# rtc.net
KiCad netlist of a schematic drawn in Altium Designer
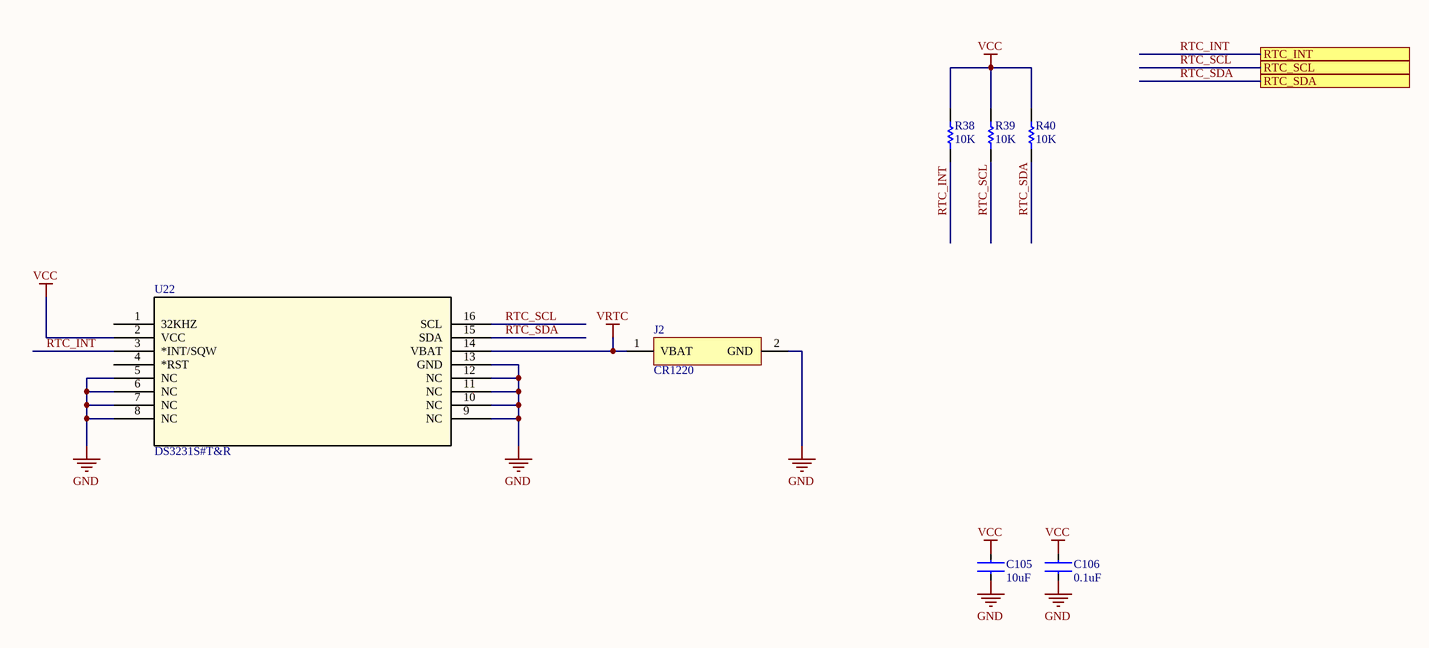
[diagram p0: rtc.SchDoc]

(export (version "E")
  (design (tool "Eeschema 10.0.6"))
  (components
    (comp (ref "C105")
      (value "10uF")
      (footprint "C0402")
      (description "Cap Ceramic 10uF 16V X7R 10% Pad SMD 1206 125°C T/R")
      (fields
        (field (name "MANUFACTURER") "Samsung")
        (field (name "MANUFACTURER PART NUMBER") "CL31B106KOHNNNE")
      )
      (libsource (lib "afra") (part "CL31B106KOHNNNE"))
    )
    (comp (ref "C106")
      (value "0.1uF")
      (footprint "C0402")
      (description "Ceramic capacitor SMD-1206 100nF /50V X7R# K +-10%, Samsung, RoHS")
      (fields
        (field (name "MANUFACTURER") "Samsung")
        (field (name "MANUFACTURER PART NUMBER") "CL31B104KBCNNNC")
      )
      (libsource (lib "afra") (part "CL31B104KBCNNNC"))
    )
    (comp (ref "J2") (value "CR1220") (footprint "CR1220 SMD") (libsource (lib "afra") (part "CR1220")))
    (comp (ref "R38")
      (value "10K")
      (footprint "R0402")
      (description "Res Thick Film 1206 10K Ohm 1% 0.25W(1/4W) ±100ppm/C Pad SMD T/R")
      (fields
        (field (name "MANUFACTURER") "Yageo")
        (field (name "MANUFACTURER PART NUMBER") "RC1206FR-0710KL")
      )
      (libsource (lib "afra") (part "RC1206FR-0710KL"))
    )
    (comp (ref "R39")
      (value "10K")
      (footprint "R0402")
      (description "Res Thick Film 1206 10K Ohm 1% 0.25W(1/4W) ±100ppm/C Pad SMD T/R")
      (fields
        (field (name "MANUFACTURER") "Yageo")
        (field (name "MANUFACTURER PART NUMBER") "RC1206FR-0710KL")
      )
      (libsource (lib "afra") (part "RC1206FR-0710KL"))
    )
    (comp (ref "R40")
      (value "10K")
      (footprint "R0402")
      (description "Res Thick Film 1206 10K Ohm 1% 0.25W(1/4W) ±100ppm/C Pad SMD T/R")
      (fields
        (field (name "MANUFACTURER") "Yageo")
        (field (name "MANUFACTURER PART NUMBER") "RC1206FR-0710KL")
      )
      (libsource (lib "afra") (part "RC1206FR-0710KL"))
    )
    (comp (ref "U22")
      (value "DS3231S#T&R")
      (footprint "21-0042B_16_MXM")
      (description "No Description Available")
      (fields (field (name "COPYRIGHT") "Copyright (C) 2022 Ultra Librarian. All rights reserved."))
      (libsource (lib "afra") (part "DS3231S#T&R"))
    )
  )
  (nets
    (net (code "1") (name "/RTC_INT") (class "Default")
      (node (ref "R38") (pin "1") (pinfunction "1_1") (pintype "passive"))
      (node (ref "U22") (pin "3") (pinfunction "*INT/SQW_3") (pintype "passive"))
    )
    (net (code "2") (name "/RTC_SCL") (class "Default")
      (node (ref "R39") (pin "1") (pinfunction "1_1") (pintype "passive"))
      (node (ref "U22") (pin "16") (pinfunction "SCL_16") (pintype "passive"))
    )
    (net (code "3") (name "/RTC_SDA") (class "Default")
      (node (ref "R40") (pin "1") (pinfunction "1_1") (pintype "passive"))
      (node (ref "U22") (pin "15") (pinfunction "SDA_15") (pintype "passive"))
    )
    (net (code "4") (name "GND") (class "Default")
      (node (ref "C105") (pin "2") (pinfunction "2_2") (pintype "passive"))
      (node (ref "C106") (pin "2") (pinfunction "2_2") (pintype "passive"))
      (node (ref "J2") (pin "2") (pinfunction "GND_2") (pintype "passive"))
      (node (ref "U22") (pin "10") (pinfunction "NC_10") (pintype "passive"))
      (node (ref "U22") (pin "11") (pinfunction "NC_11") (pintype "passive"))
      (node (ref "U22") (pin "12") (pinfunction "NC_12") (pintype "passive"))
      (node (ref "U22") (pin "13") (pinfunction "GND_13") (pintype "power_in"))
      (node (ref "U22") (pin "5") (pinfunction "NC_5") (pintype "passive"))
      (node (ref "U22") (pin "6") (pinfunction "NC_6") (pintype "passive"))
      (node (ref "U22") (pin "7") (pinfunction "NC_7") (pintype "passive"))
      (node (ref "U22") (pin "8") (pinfunction "NC_8") (pintype "passive"))
      (node (ref "U22") (pin "9") (pinfunction "NC_9") (pintype "passive"))
    )
    (net (code "5") (name "VCC") (class "Default")
      (node (ref "C105") (pin "1") (pinfunction "1_1") (pintype "passive"))
      (node (ref "C106") (pin "1") (pinfunction "1_1") (pintype "passive"))
      (node (ref "R38") (pin "2") (pinfunction "2_2") (pintype "passive"))
      (node (ref "R39") (pin "2") (pinfunction "2_2") (pintype "passive"))
      (node (ref "R40") (pin "2") (pinfunction "2_2") (pintype "passive"))
      (node (ref "U22") (pin "2") (pinfunction "VCC_2") (pintype "power_in"))
    )
    (net (code "6") (name "VRTC") (class "Default")
      (node (ref "J2") (pin "1") (pinfunction "VBAT_1") (pintype "passive"))
      (node (ref "U22") (pin "14") (pinfunction "VBAT_14") (pintype "power_in"))
    )
    (net (code "7") (name "unconnected-(U22-*RST-Pad4)") (class "Default")
      (node (ref "U22") (pin "4") (pinfunction "*RST_4") (pintype "passive"))
    )
    (net (code "8") (name "unconnected-(U22-32KHZ-Pad1)") (class "Default")
      (node (ref "U22") (pin "1") (pinfunction "32KHZ_1") (pintype "passive"))
    )
  )
)
